# Voltage_Sources.net
KiCad netlist of a schematic drawn in Altium Designer
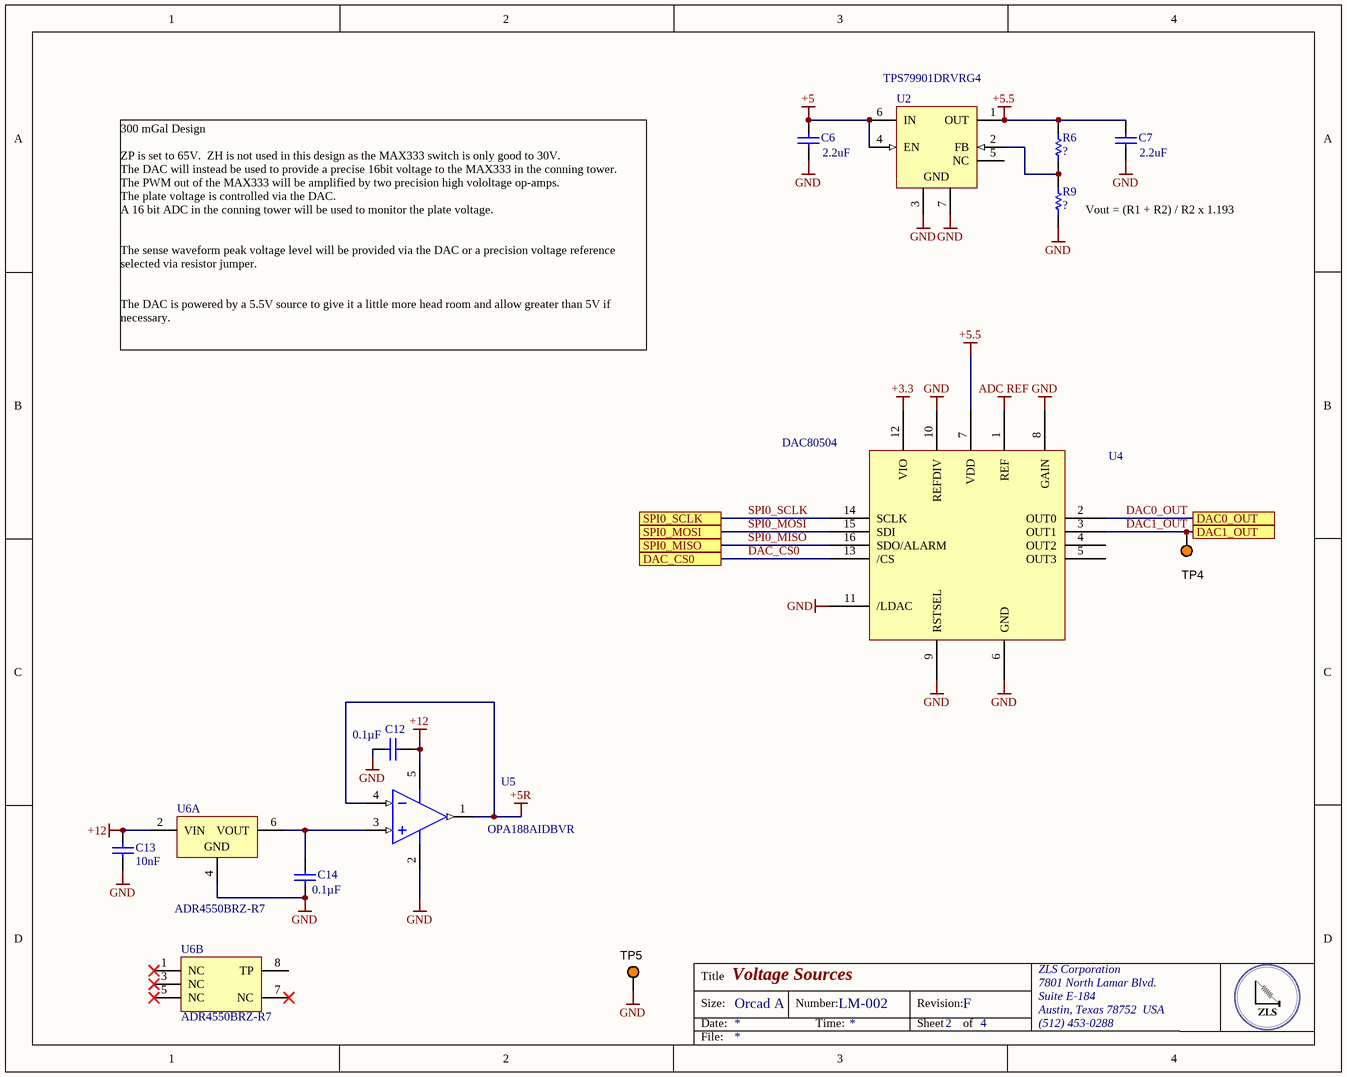
[diagram p0: Voltage_Sources.SchDoc]

(export (version "E")
  (design (tool "Eeschema 10.0.6"))
  (components
    (comp (ref "C6")
      (value "CAP CER 1UF 25V X7R 0805")
      (footprint "CAPC0805(2012)155_L")
      (fields
        (field (name "MANUFACTURER") "Murata Electronics North America")
        (field (name "MANUFACTURER PART NUMBER") "GRM21BR71E105KA99L")
        (field (name "CAPACITANCE") "2.2uF")
        (field (name "TOLERANCE") "±10%")
      )
      (libsource (lib "Altium Content Vault") (part "CMP-1036-04882-1"))
    )
    (comp (ref "C7")
      (value "CAP CER 1UF 25V X7R 0805")
      (footprint "CAPC0805(2012)155_L")
      (fields
        (field (name "MANUFACTURER") "Murata Electronics North America")
        (field (name "MANUFACTURER PART NUMBER") "GRM21BR71E105KA99L")
        (field (name "CAPACITANCE") "2.2uF")
        (field (name "TOLERANCE") "±10%")
      )
      (libsource (lib "Altium Content Vault") (part "CMP-1036-04882-1"))
    )
    (comp (ref "C12")
      (value "CAP CER 0.1UF 25V X7R 0805")
      (footprint "CAPC0805(2012)145_N")
      (fields
        (field (name "MANUFACTURER") "Murata Electronics North America")
        (field (name "MANUFACTURER PART NUMBER") "GRM21BR71E104KA01L")
        (field (name "CAPACITANCE") "0.1µF")
        (field (name "TOLERANCE") "±10%")
      )
      (libsource (lib "Altium Content Vault") (part "CMP-1036-04795-1"))
    )
    (comp (ref "C13")
      (value "Multilayer Ceramic Capacitors MLCC - SMD/SMT 0.01uF 50volts 10% X7R")
      (footprint "CAPC0805(2012)145_N")
      (fields
        (field (name "MANUFACTURER") "Kemet")
        (field (name "MANUFACTURER PART NUMBER") "C0805C103K5RACAUTO")
        (field (name "CAPACITANCE") "10nF")
        (field (name "TOLERANCE") "10%")
      )
      (libsource (lib "Altium Content Vault") (part "CMP-1036-04795-1"))
    )
    (comp (ref "C14")
      (value "CAP CER 0.1UF 25V X7R 0805")
      (footprint "CAPC0805(2012)145_N")
      (fields
        (field (name "MANUFACTURER") "Murata Electronics North America")
        (field (name "MANUFACTURER PART NUMBER") "GRM21BR71E104KA01L")
        (field (name "CAPACITANCE") "0.1µF")
        (field (name "TOLERANCE") "±10%")
      )
      (libsource (lib "Altium Content Vault") (part "CMP-1036-04795-1"))
    )
    (comp (ref "R6")
      (value "?")
      (footprint "RESC0805(2012)_L")
      (libsource (lib "Altium Content Vault") (part "CMP-1013-00215-1"))
    )
    (comp (ref "R9")
      (value "?")
      (footprint "RESC0805(2012)_L")
      (libsource (lib "Altium Content Vault") (part "CMP-1013-00215-1"))
    )
    (comp (ref "TP4")
      (value "5003")
      (footprint "KSTN-5003")
      (description "Test Point, Orange, 1-Pin THD, RoHS")
      (libsource (lib "Altium Content Vault") (part "CMP-1672-00009-1"))
    )
    (comp (ref "TP5")
      (value "5003")
      (footprint "KSTN-5003")
      (description "Test Point, Orange, 1-Pin THD, RoHS")
      (libsource (lib "Altium Content Vault") (part "CMP-1672-00009-1"))
    )
    (comp (ref "U2")
      (value "TPS79901DRVRG4")
      (footprint "TI-DRV6-1600X1000TP_V")
      (fields (field (name "MANUFACTURER") "Texas Instruments"))
      (libsource (lib "Altium Content Vault") (part "TI-TPS7XXXXDRV6-1600X1000TP"))
    )
    (comp (ref "U4")
      (value "DAC80504")
      (footprint "DAC80504")
      (libsource (lib "ZLS_Schematic_lib") (part "DAC80504"))
    )
    (comp (ref "U5")
      (value "OPA188AIDBVR")
      (footprint "DBV0005A_M")
      (fields (field (name "MANUFACTURER") "Texas Instruments"))
      (libsource (lib "Altium Content Vault") (part "CMP-0809-00005-2"))
    )
    (comp (ref "U6")
      (value "ADR4550BRZ-R7")
      (footprint "ADI-R-8_M")
      (fields (field (name "MANUFACTURER") "Analog Devices"))
      (libsource (lib "Altium Content Vault") (part "ADI-ADR45xx-R-8"))
    )
  )
  (nets
    (net (code "1") (name "+3.3") (class "Default")
      (node (ref "U4") (pin "12") (pinfunction "VIO_12") (pintype "passive"))
    )
    (net (code "2") (name "+5") (class "Default")
      (node (ref "C6") (pin "2") (pinfunction "2_2") (pintype "passive"))
      (node (ref "U2") (pin "4") (pinfunction "EN_4") (pintype "input"))
      (node (ref "U2") (pin "6") (pinfunction "IN_6") (pintype "power_in"))
    )
    (net (code "3") (name "+5.5") (class "Default")
      (node (ref "C7") (pin "2") (pinfunction "2_2") (pintype "passive"))
      (node (ref "R6") (pin "1") (pinfunction "1_1") (pintype "passive"))
      (node (ref "U2") (pin "1") (pinfunction "OUT_1") (pintype "power_in"))
      (node (ref "U4") (pin "7") (pinfunction "VDD_7") (pintype "passive"))
    )
    (net (code "4") (name "+5R") (class "Default")
      (node (ref "U5") (pin "1") (pinfunction "OUT_1") (pintype "output"))
      (node (ref "U5") (pin "4") (pinfunction "IN-_4") (pintype "input"))
    )
    (net (code "5") (name "+12") (class "Default")
      (node (ref "C12") (pin "2") (pinfunction "2_2") (pintype "passive"))
      (node (ref "C13") (pin "1") (pinfunction "1_1") (pintype "passive"))
      (node (ref "U5") (pin "5") (pinfunction "V+_5") (pintype "power_in"))
      (node (ref "U6") (pin "2") (pinfunction "VIN_2") (pintype "power_in"))
    )
    (net (code "6") (name "/DAC0_OUT") (class "Default")
      (node (ref "U4") (pin "2") (pinfunction "OUT0_2") (pintype "passive"))
    )
    (net (code "7") (name "/DAC1_OUT") (class "Default")
      (node (ref "TP4") (pin "1") (pinfunction "1_1") (pintype "passive"))
      (node (ref "U4") (pin "3") (pinfunction "OUT1_3") (pintype "passive"))
    )
    (net (code "8") (name "/DAC_CS0") (class "Default")
      (node (ref "U4") (pin "13") (pinfunction "/CS_13") (pintype "passive"))
    )
    (net (code "9") (name "/SPI0_MISO") (class "Default")
      (node (ref "U4") (pin "16") (pinfunction "SDO/ALARM_16") (pintype "passive"))
    )
    (net (code "10") (name "/SPI0_MOSI") (class "Default")
      (node (ref "U4") (pin "15") (pinfunction "SDI_15") (pintype "passive"))
    )
    (net (code "11") (name "/SPI0_SCLK") (class "Default")
      (node (ref "U4") (pin "14") (pinfunction "SCLK_14") (pintype "passive"))
    )
    (net (code "12") (name "ADC REF") (class "Default")
      (node (ref "U4") (pin "1") (pinfunction "REF_1") (pintype "passive"))
    )
    (net (code "13") (name "GND") (class "Default")
      (node (ref "C12") (pin "1") (pinfunction "1_1") (pintype "passive"))
      (node (ref "C13") (pin "2") (pinfunction "2_2") (pintype "passive"))
      (node (ref "C14") (pin "2") (pinfunction "2_2") (pintype "passive"))
      (node (ref "C6") (pin "1") (pinfunction "1_1") (pintype "passive"))
      (node (ref "C7") (pin "1") (pinfunction "1_1") (pintype "passive"))
      (node (ref "R9") (pin "2") (pinfunction "2_2") (pintype "passive"))
      (node (ref "TP5") (pin "1") (pinfunction "1_1") (pintype "passive"))
      (node (ref "U2") (pin "3") (pinfunction "GND_3") (pintype "power_in"))
      (node (ref "U2") (pin "7") (pinfunction "GND_7") (pintype "power_in"))
      (node (ref "U4") (pin "10") (pinfunction "REFDIV_10") (pintype "passive"))
      (node (ref "U4") (pin "11") (pinfunction "/LDAC_11") (pintype "passive"))
      (node (ref "U4") (pin "6") (pinfunction "GND_6") (pintype "passive"))
      (node (ref "U4") (pin "8") (pinfunction "GAIN_8") (pintype "passive"))
      (node (ref "U4") (pin "9") (pinfunction "RSTSEL_9") (pintype "passive"))
      (node (ref "U5") (pin "2") (pinfunction "V-_2") (pintype "power_in"))
      (node (ref "U6") (pin "4") (pinfunction "GND_4") (pintype "power_in"))
    )
    (net (code "14") (name "Net-(U2-FB)") (class "Default")
      (node (ref "R6") (pin "2") (pinfunction "2_2") (pintype "passive"))
      (node (ref "R9") (pin "1") (pinfunction "1_1") (pintype "passive"))
      (node (ref "U2") (pin "2") (pinfunction "FB_2") (pintype "input"))
    )
    (net (code "15") (name "Net-(U5-IN+)") (class "Default")
      (node (ref "C14") (pin "1") (pinfunction "1_1") (pintype "passive"))
      (node (ref "U5") (pin "3") (pinfunction "IN+_3") (pintype "input"))
      (node (ref "U6") (pin "6") (pinfunction "VOUT_6") (pintype "power_in"))
    )
    (net (code "16") (name "unconnected-(U2-NC-Pad5)") (class "Default")
      (node (ref "U2") (pin "5") (pinfunction "NC_5") (pintype "passive"))
    )
    (net (code "17") (name "unconnected-(U4-OUT2-Pad4)") (class "Default")
      (node (ref "U4") (pin "4") (pinfunction "OUT2_4") (pintype "passive"))
    )
    (net (code "18") (name "unconnected-(U4-OUT3-Pad5)") (class "Default")
      (node (ref "U4") (pin "5") (pinfunction "OUT3_5") (pintype "passive"))
    )
    (net (code "19") (name "unconnected-(U6B-NC-Pad1)") (class "Default")
      (node (ref "U6") (pin "1") (pinfunction "NC_1") (pintype "passive+no_connect"))
    )
    (net (code "20") (name "unconnected-(U6B-NC-Pad3)") (class "Default")
      (node (ref "U6") (pin "3") (pinfunction "NC_3") (pintype "passive+no_connect"))
    )
    (net (code "21") (name "unconnected-(U6B-NC-Pad5)") (class "Default")
      (node (ref "U6") (pin "5") (pinfunction "NC_5") (pintype "passive+no_connect"))
    )
    (net (code "22") (name "unconnected-(U6B-NC-Pad7)") (class "Default")
      (node (ref "U6") (pin "7") (pinfunction "NC_7") (pintype "passive+no_connect"))
    )
    (net (code "23") (name "unconnected-(U6B-TP-Pad8)") (class "Default")
      (node (ref "U6") (pin "8") (pinfunction "TP_8") (pintype "passive"))
    )
  )
)
